# SCIENCE.net
KiCad netlist of a schematic drawn in Altium Designer
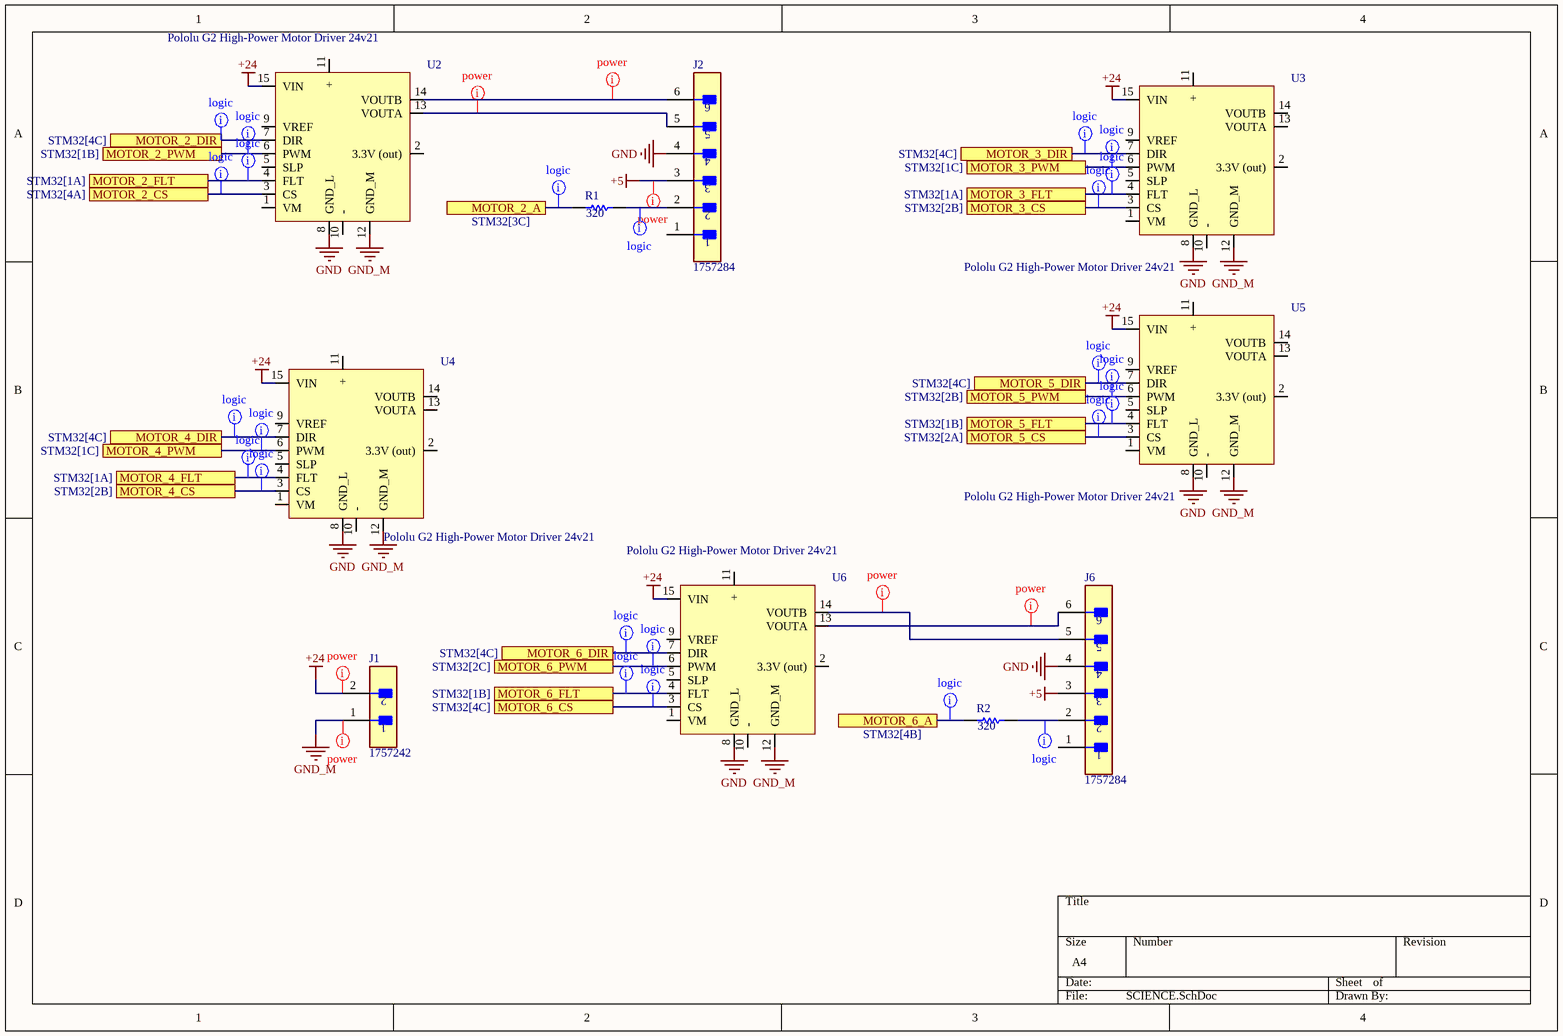
[diagram p0: SCIENCE.SchDoc]

(export (version "E")
  (design (tool "Eeschema 10.0.6"))
  (components
    (comp (ref "J1")
      (value "1757242")
      (footprint "FP-1757242-MFG")
      (description "TERM BLOCK HDR 2POS 90DEG 5.08MM")
      (fields (field (name "VOLTAGE") "300V"))
      (libsource (lib "Phoenix") (part "CMP-09399-000010-1"))
    )
    (comp (ref "J2")
      (value "1757284")
      (footprint "FP-1757284-MFG")
      (description "TERM BLOCK HDR 6POS 90DEG 5.08MM")
      (fields (field (name "VOLTAGE") "300V"))
      (libsource (lib "Phoenix") (part "CMP-09399-000007-1"))
    )
    (comp (ref "J6")
      (value "1757284")
      (footprint "FP-1757284-MFG")
      (description "TERM BLOCK HDR 6POS 90DEG 5.08MM")
      (fields (field (name "VOLTAGE") "300V"))
      (libsource (lib "Phoenix") (part "CMP-09399-000007-1"))
    )
    (comp (ref "R1")
      (value "320")
      (footprint "AXIAL-0.3")
      (description "Resistor")
      (fields (field (name "Comment") "Res1") (field (name "PUBLISHER") "Altium Limited"))
      (libsource (lib "Miscellaneous Devices") (part "Res1"))
    )
    (comp (ref "R2")
      (value "320")
      (footprint "AXIAL-0.3")
      (description "Resistor")
      (fields (field (name "Comment") "Res1") (field (name "PUBLISHER") "Altium Limited"))
      (libsource (lib "Miscellaneous Devices") (part "Res1"))
    )
    (comp (ref "U2")
      (value "Pololu G2 High-Power Motor Driver 24v21")
      (footprint "Pololu G2 High-Power Motor Driver 24v21")
      (libsource (lib "DC motors drivers") (part "Pololu G2 High-Power Motor Driver 24v21"))
    )
    (comp (ref "U3")
      (value "Pololu G2 High-Power Motor Driver 24v21")
      (footprint "Pololu G2 High-Power Motor Driver 24v21")
      (libsource (lib "DC motors drivers") (part "Pololu G2 High-Power Motor Driver 24v21"))
    )
    (comp (ref "U4")
      (value "Pololu G2 High-Power Motor Driver 24v21")
      (footprint "Pololu G2 High-Power Motor Driver 24v21")
      (libsource (lib "DC motors drivers") (part "Pololu G2 High-Power Motor Driver 24v21"))
    )
    (comp (ref "U5")
      (value "Pololu G2 High-Power Motor Driver 24v21")
      (footprint "Pololu G2 High-Power Motor Driver 24v21")
      (libsource (lib "DC motors drivers") (part "Pololu G2 High-Power Motor Driver 24v21"))
    )
    (comp (ref "U6")
      (value "Pololu G2 High-Power Motor Driver 24v21")
      (footprint "Pololu G2 High-Power Motor Driver 24v21")
      (libsource (lib "DC motors drivers") (part "Pololu G2 High-Power Motor Driver 24v21"))
    )
  )
  (nets
    (net (code "1") (name "+5") (class "Default")
      (node (ref "J2") (pin "3") (pinfunction "3_3") (pintype "passive"))
      (node (ref "J6") (pin "3") (pinfunction "3_3") (pintype "passive"))
    )
    (net (code "2") (name "+24") (class "Default")
      (node (ref "J1") (pin "2") (pinfunction "2_2") (pintype "passive"))
      (node (ref "U2") (pin "15") (pinfunction "VIN_15") (pintype "passive"))
      (node (ref "U3") (pin "15") (pinfunction "VIN_15") (pintype "passive"))
      (node (ref "U4") (pin "15") (pinfunction "VIN_15") (pintype "passive"))
      (node (ref "U5") (pin "15") (pinfunction "VIN_15") (pintype "passive"))
      (node (ref "U6") (pin "15") (pinfunction "VIN_15") (pintype "passive"))
    )
    (net (code "3") (name "/MOTOR_2_A") (class "Default")
      (node (ref "R1") (pin "1") (pinfunction "1_1") (pintype "passive"))
    )
    (net (code "4") (name "/MOTOR_2_CS") (class "Default")
      (node (ref "U2") (pin "3") (pinfunction "CS_3") (pintype "passive"))
    )
    (net (code "5") (name "/MOTOR_2_DIR") (class "Default")
      (node (ref "U2") (pin "7") (pinfunction "DIR_7") (pintype "passive"))
    )
    (net (code "6") (name "/MOTOR_2_FLT") (class "Default")
      (node (ref "U2") (pin "4") (pinfunction "FLT_4") (pintype "passive"))
    )
    (net (code "7") (name "/MOTOR_2_PWM") (class "Default")
      (node (ref "U2") (pin "6") (pinfunction "PWM_6") (pintype "passive"))
    )
    (net (code "8") (name "/MOTOR_3_CS") (class "Default")
      (node (ref "U3") (pin "3") (pinfunction "CS_3") (pintype "passive"))
    )
    (net (code "9") (name "/MOTOR_3_DIR") (class "Default")
      (node (ref "U3") (pin "7") (pinfunction "DIR_7") (pintype "passive"))
    )
    (net (code "10") (name "/MOTOR_3_FLT") (class "Default")
      (node (ref "U3") (pin "4") (pinfunction "FLT_4") (pintype "passive"))
    )
    (net (code "11") (name "/MOTOR_3_PWM") (class "Default")
      (node (ref "U3") (pin "6") (pinfunction "PWM_6") (pintype "passive"))
    )
    (net (code "12") (name "/MOTOR_4_CS") (class "Default")
      (node (ref "U4") (pin "3") (pinfunction "CS_3") (pintype "passive"))
    )
    (net (code "13") (name "/MOTOR_4_DIR") (class "Default")
      (node (ref "U4") (pin "7") (pinfunction "DIR_7") (pintype "passive"))
    )
    (net (code "14") (name "/MOTOR_4_FLT") (class "Default")
      (node (ref "U4") (pin "4") (pinfunction "FLT_4") (pintype "passive"))
    )
    (net (code "15") (name "/MOTOR_4_PWM") (class "Default")
      (node (ref "U4") (pin "6") (pinfunction "PWM_6") (pintype "passive"))
    )
    (net (code "16") (name "/MOTOR_5_CS") (class "Default")
      (node (ref "U5") (pin "3") (pinfunction "CS_3") (pintype "passive"))
    )
    (net (code "17") (name "/MOTOR_5_DIR") (class "Default")
      (node (ref "U5") (pin "7") (pinfunction "DIR_7") (pintype "passive"))
    )
    (net (code "18") (name "/MOTOR_5_FLT") (class "Default")
      (node (ref "U5") (pin "4") (pinfunction "FLT_4") (pintype "passive"))
    )
    (net (code "19") (name "/MOTOR_5_PWM") (class "Default")
      (node (ref "U5") (pin "6") (pinfunction "PWM_6") (pintype "passive"))
    )
    (net (code "20") (name "/MOTOR_6_A") (class "Default")
      (node (ref "R2") (pin "1") (pinfunction "1_1") (pintype "passive"))
    )
    (net (code "21") (name "/MOTOR_6_CS") (class "Default")
      (node (ref "U6") (pin "3") (pinfunction "CS_3") (pintype "passive"))
    )
    (net (code "22") (name "/MOTOR_6_DIR") (class "Default")
      (node (ref "U6") (pin "7") (pinfunction "DIR_7") (pintype "passive"))
    )
    (net (code "23") (name "/MOTOR_6_FLT") (class "Default")
      (node (ref "U6") (pin "4") (pinfunction "FLT_4") (pintype "passive"))
    )
    (net (code "24") (name "/MOTOR_6_PWM") (class "Default")
      (node (ref "U6") (pin "6") (pinfunction "PWM_6") (pintype "passive"))
    )
    (net (code "25") (name "GND") (class "Default")
      (node (ref "J2") (pin "4") (pinfunction "4_4") (pintype "passive"))
      (node (ref "J6") (pin "4") (pinfunction "4_4") (pintype "passive"))
      (node (ref "U2") (pin "8") (pinfunction "GND_L_8") (pintype "passive"))
      (node (ref "U3") (pin "8") (pinfunction "GND_L_8") (pintype "passive"))
      (node (ref "U4") (pin "8") (pinfunction "GND_L_8") (pintype "passive"))
      (node (ref "U5") (pin "8") (pinfunction "GND_L_8") (pintype "passive"))
      (node (ref "U6") (pin "8") (pinfunction "GND_L_8") (pintype "passive"))
    )
    (net (code "26") (name "GND_M") (class "Default")
      (node (ref "J1") (pin "1") (pinfunction "1_1") (pintype "passive"))
      (node (ref "U2") (pin "12") (pinfunction "GND_M_12") (pintype "passive"))
      (node (ref "U3") (pin "12") (pinfunction "GND_M_12") (pintype "passive"))
      (node (ref "U4") (pin "12") (pinfunction "GND_M_12") (pintype "passive"))
      (node (ref "U5") (pin "12") (pinfunction "GND_M_12") (pintype "passive"))
      (node (ref "U6") (pin "12") (pinfunction "GND_M_12") (pintype "passive"))
    )
    (net (code "27") (name "Net-(J2-Pad2)") (class "Default")
      (node (ref "J2") (pin "2") (pinfunction "2_2") (pintype "passive"))
      (node (ref "R1") (pin "2") (pinfunction "2_2") (pintype "passive"))
    )
    (net (code "28") (name "Net-(J6-Pad2)") (class "Default")
      (node (ref "J6") (pin "2") (pinfunction "2_2") (pintype "passive"))
      (node (ref "R2") (pin "2") (pinfunction "2_2") (pintype "passive"))
    )
    (net (code "29") (name "Net-(U2-VOUTA)") (class "Default")
      (node (ref "J2") (pin "5") (pinfunction "5_5") (pintype "passive"))
      (node (ref "U2") (pin "13") (pinfunction "VOUTA_13") (pintype "passive"))
    )
    (net (code "30") (name "Net-(U2-VOUTB)") (class "Default")
      (node (ref "J2") (pin "6") (pinfunction "6_6") (pintype "passive"))
      (node (ref "U2") (pin "14") (pinfunction "VOUTB_14") (pintype "passive"))
    )
    (net (code "31") (name "Net-(U6-VOUTA)") (class "Default")
      (node (ref "J6") (pin "6") (pinfunction "6_6") (pintype "passive"))
      (node (ref "U6") (pin "13") (pinfunction "VOUTA_13") (pintype "passive"))
    )
    (net (code "32") (name "Net-(U6-VOUTB)") (class "Default")
      (node (ref "J6") (pin "5") (pinfunction "5_5") (pintype "passive"))
      (node (ref "U6") (pin "14") (pinfunction "VOUTB_14") (pintype "passive"))
    )
    (net (code "33") (name "unconnected-(J2-Pad1)") (class "Default")
      (node (ref "J2") (pin "1") (pinfunction "1_1") (pintype "passive"))
    )
    (net (code "34") (name "unconnected-(J6-Pad1)") (class "Default")
      (node (ref "J6") (pin "1") (pinfunction "1_1") (pintype "passive"))
    )
    (net (code "35") (name "unconnected-(U2-+-Pad11)") (class "Default")
      (node (ref "U2") (pin "11") (pinfunction "+_11") (pintype "passive"))
    )
    (net (code "36") (name "unconnected-(U2---Pad10)") (class "Default")
      (node (ref "U2") (pin "10") (pinfunction "-_10") (pintype "passive"))
    )
    (net (code "37") (name "unconnected-(U2-3.3V_(out)-Pad2)") (class "Default")
      (node (ref "U2") (pin "2") (pinfunction "3.3V_(out)_2") (pintype "passive"))
    )
    (net (code "38") (name "unconnected-(U2-SLP-Pad5)") (class "Default")
      (node (ref "U2") (pin "5") (pinfunction "SLP_5") (pintype "passive"))
    )
    (net (code "39") (name "unconnected-(U2-VM-Pad1)") (class "Default")
      (node (ref "U2") (pin "1") (pinfunction "VM_1") (pintype "passive"))
    )
    (net (code "40") (name "unconnected-(U2-VREF-Pad9)") (class "Default")
      (node (ref "U2") (pin "9") (pinfunction "VREF_9") (pintype "passive"))
    )
    (net (code "41") (name "unconnected-(U3-+-Pad11)") (class "Default")
      (node (ref "U3") (pin "11") (pinfunction "+_11") (pintype "passive"))
    )
    (net (code "42") (name "unconnected-(U3---Pad10)") (class "Default")
      (node (ref "U3") (pin "10") (pinfunction "-_10") (pintype "passive"))
    )
    (net (code "43") (name "unconnected-(U3-3.3V_(out)-Pad2)") (class "Default")
      (node (ref "U3") (pin "2") (pinfunction "3.3V_(out)_2") (pintype "passive"))
    )
    (net (code "44") (name "unconnected-(U3-SLP-Pad5)") (class "Default")
      (node (ref "U3") (pin "5") (pinfunction "SLP_5") (pintype "passive"))
    )
    (net (code "45") (name "unconnected-(U3-VM-Pad1)") (class "Default")
      (node (ref "U3") (pin "1") (pinfunction "VM_1") (pintype "passive"))
    )
    (net (code "46") (name "unconnected-(U3-VOUTA-Pad13)") (class "Default")
      (node (ref "U3") (pin "13") (pinfunction "VOUTA_13") (pintype "passive"))
    )
    (net (code "47") (name "unconnected-(U3-VOUTB-Pad14)") (class "Default")
      (node (ref "U3") (pin "14") (pinfunction "VOUTB_14") (pintype "passive"))
    )
    (net (code "48") (name "unconnected-(U3-VREF-Pad9)") (class "Default")
      (node (ref "U3") (pin "9") (pinfunction "VREF_9") (pintype "passive"))
    )
    (net (code "49") (name "unconnected-(U4-+-Pad11)") (class "Default")
      (node (ref "U4") (pin "11") (pinfunction "+_11") (pintype "passive"))
    )
    (net (code "50") (name "unconnected-(U4---Pad10)") (class "Default")
      (node (ref "U4") (pin "10") (pinfunction "-_10") (pintype "passive"))
    )
    (net (code "51") (name "unconnected-(U4-3.3V_(out)-Pad2)") (class "Default")
      (node (ref "U4") (pin "2") (pinfunction "3.3V_(out)_2") (pintype "passive"))
    )
    (net (code "52") (name "unconnected-(U4-SLP-Pad5)") (class "Default")
      (node (ref "U4") (pin "5") (pinfunction "SLP_5") (pintype "passive"))
    )
    (net (code "53") (name "unconnected-(U4-VM-Pad1)") (class "Default")
      (node (ref "U4") (pin "1") (pinfunction "VM_1") (pintype "passive"))
    )
    (net (code "54") (name "unconnected-(U4-VOUTA-Pad13)") (class "Default")
      (node (ref "U4") (pin "13") (pinfunction "VOUTA_13") (pintype "passive"))
    )
    (net (code "55") (name "unconnected-(U4-VOUTB-Pad14)") (class "Default")
      (node (ref "U4") (pin "14") (pinfunction "VOUTB_14") (pintype "passive"))
    )
    (net (code "56") (name "unconnected-(U4-VREF-Pad9)") (class "Default")
      (node (ref "U4") (pin "9") (pinfunction "VREF_9") (pintype "passive"))
    )
    (net (code "57") (name "unconnected-(U5-+-Pad11)") (class "Default")
      (node (ref "U5") (pin "11") (pinfunction "+_11") (pintype "passive"))
    )
    (net (code "58") (name "unconnected-(U5---Pad10)") (class "Default")
      (node (ref "U5") (pin "10") (pinfunction "-_10") (pintype "passive"))
    )
    (net (code "59") (name "unconnected-(U5-3.3V_(out)-Pad2)") (class "Default")
      (node (ref "U5") (pin "2") (pinfunction "3.3V_(out)_2") (pintype "passive"))
    )
    (net (code "60") (name "unconnected-(U5-SLP-Pad5)") (class "Default")
      (node (ref "U5") (pin "5") (pinfunction "SLP_5") (pintype "passive"))
    )
    (net (code "61") (name "unconnected-(U5-VM-Pad1)") (class "Default")
      (node (ref "U5") (pin "1") (pinfunction "VM_1") (pintype "passive"))
    )
    (net (code "62") (name "unconnected-(U5-VOUTA-Pad13)") (class "Default")
      (node (ref "U5") (pin "13") (pinfunction "VOUTA_13") (pintype "passive"))
    )
    (net (code "63") (name "unconnected-(U5-VOUTB-Pad14)") (class "Default")
      (node (ref "U5") (pin "14") (pinfunction "VOUTB_14") (pintype "passive"))
    )
    (net (code "64") (name "unconnected-(U5-VREF-Pad9)") (class "Default")
      (node (ref "U5") (pin "9") (pinfunction "VREF_9") (pintype "passive"))
    )
    (net (code "65") (name "unconnected-(U6-+-Pad11)") (class "Default")
      (node (ref "U6") (pin "11") (pinfunction "+_11") (pintype "passive"))
    )
    (net (code "66") (name "unconnected-(U6---Pad10)") (class "Default")
      (node (ref "U6") (pin "10") (pinfunction "-_10") (pintype "passive"))
    )
    (net (code "67") (name "unconnected-(U6-3.3V_(out)-Pad2)") (class "Default")
      (node (ref "U6") (pin "2") (pinfunction "3.3V_(out)_2") (pintype "passive"))
    )
    (net (code "68") (name "unconnected-(U6-SLP-Pad5)") (class "Default")
      (node (ref "U6") (pin "5") (pinfunction "SLP_5") (pintype "passive"))
    )
    (net (code "69") (name "unconnected-(U6-VM-Pad1)") (class "Default")
      (node (ref "U6") (pin "1") (pinfunction "VM_1") (pintype "passive"))
    )
    (net (code "70") (name "unconnected-(U6-VREF-Pad9)") (class "Default")
      (node (ref "U6") (pin "9") (pinfunction "VREF_9") (pintype "passive"))
    )
  )
)
